# Schema.net
KiCad netlist of a schematic drawn in Altium Designer
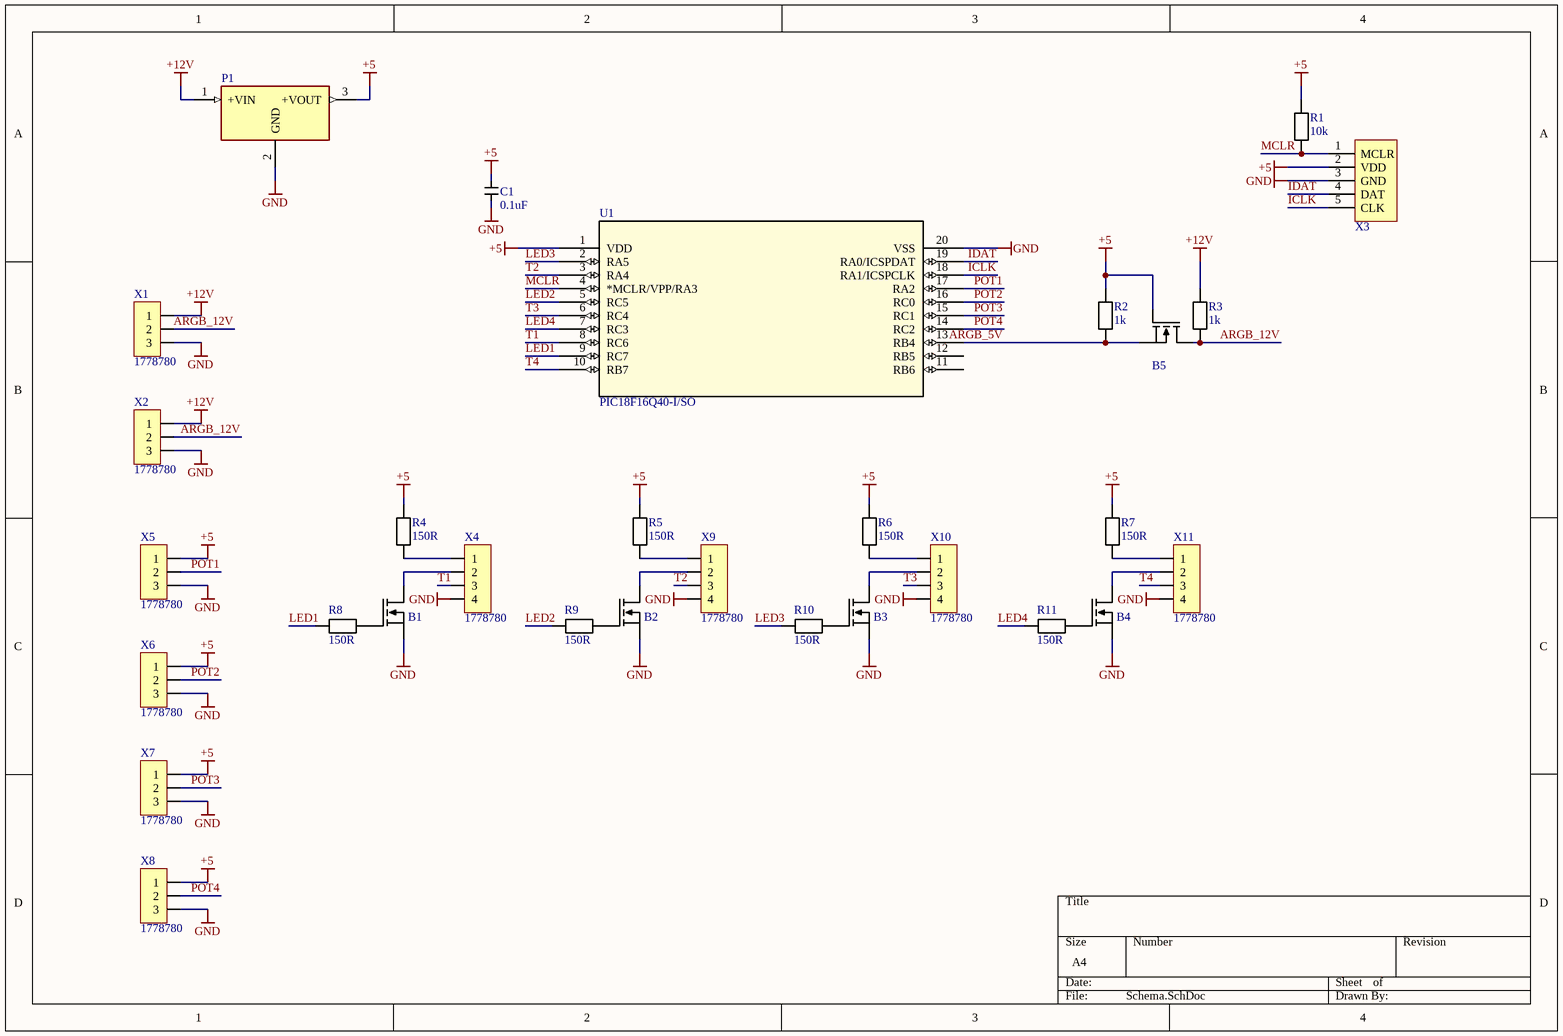
[diagram p0: Schema.SchDoc]

(export (version "E")
  (design (tool "Eeschema 10.0.6"))
  (components
    (comp (ref "B1")
      (value "N Kanal FET")
      (footprint "GeneralPCBLibrary:SOT23-3")
      (libsource (lib "GeneralSchemaLibrary") (part "N Kanal FET"))
    )
    (comp (ref "B2")
      (value "N Kanal FET")
      (footprint "GeneralPCBLibrary:SOT23-3")
      (libsource (lib "GeneralSchemaLibrary") (part "N Kanal FET"))
    )
    (comp (ref "B3")
      (value "N Kanal FET")
      (footprint "GeneralPCBLibrary:SOT23-3")
      (libsource (lib "GeneralSchemaLibrary") (part "N Kanal FET"))
    )
    (comp (ref "B4")
      (value "N Kanal FET")
      (footprint "GeneralPCBLibrary:SOT23-3")
      (libsource (lib "GeneralSchemaLibrary") (part "N Kanal FET"))
    )
    (comp (ref "B5")
      (value "N Kanal FET")
      (footprint "GeneralPCBLibrary:SOT23-3")
      (libsource (lib "GeneralSchemaLibrary") (part "N Kanal FET"))
    )
    (comp (ref "C1")
      (value "0.1uF")
      (footprint "GeneralPCBLibrary:CAP CER 0805 H")
      (fields (field (name "Comment") "Capacitor 0805"))
      (libsource (lib "GeneralSchemaLibrary") (part "Capacitor 0805"))
    )
    (comp (ref "P1")
      (value "TSR_1-2450")
      (footprint "GeneralPCBLibrary:TSR_1-2450")
      (description "1 Amp POL switching regulator, 4.6 to -36 VDC input, pos.-pos. circuit, LM78 compatible, SIP-3")
      (fields (field (name "MF") "Traco Power") (field (name "MP") "TSR 1-2450"))
      (libsource (lib "GeneralSchemaLibrary") (part "TSR_1-2450"))
    )
    (comp (ref "R1")
      (value "10k")
      (footprint "GeneralPCBLibrary:RES 0603 H")
      (fields (field (name "Comment") "Resistor 0603"))
      (libsource (lib "GeneralSchemaLibrary") (part "Resistor 0603"))
    )
    (comp (ref "R2")
      (value "1k")
      (footprint "GeneralPCBLibrary:RES 0603 H")
      (fields (field (name "Comment") "Resistor 0603"))
      (libsource (lib "GeneralSchemaLibrary") (part "Resistor 0603"))
    )
    (comp (ref "R3")
      (value "1k")
      (footprint "GeneralPCBLibrary:RES 0603 H")
      (fields (field (name "Comment") "Resistor 0603"))
      (libsource (lib "GeneralSchemaLibrary") (part "Resistor 0603"))
    )
    (comp (ref "R4")
      (value "150R")
      (footprint "GeneralPCBLibrary:RES 0603 H")
      (fields (field (name "Comment") "Resistor 0603"))
      (libsource (lib "GeneralSchemaLibrary") (part "Resistor 0603"))
    )
    (comp (ref "R5")
      (value "150R")
      (footprint "GeneralPCBLibrary:RES 0603 H")
      (fields (field (name "Comment") "Resistor 0603"))
      (libsource (lib "GeneralSchemaLibrary") (part "Resistor 0603"))
    )
    (comp (ref "R6")
      (value "150R")
      (footprint "GeneralPCBLibrary:RES 0603 H")
      (fields (field (name "Comment") "Resistor 0603"))
      (libsource (lib "GeneralSchemaLibrary") (part "Resistor 0603"))
    )
    (comp (ref "R7")
      (value "150R")
      (footprint "GeneralPCBLibrary:RES 0603 H")
      (fields (field (name "Comment") "Resistor 0603"))
      (libsource (lib "GeneralSchemaLibrary") (part "Resistor 0603"))
    )
    (comp (ref "R8")
      (value "150R")
      (footprint "GeneralPCBLibrary:RES 0603 H")
      (fields (field (name "Comment") "Resistor 0603"))
      (libsource (lib "GeneralSchemaLibrary") (part "Resistor 0603"))
    )
    (comp (ref "R9")
      (value "150R")
      (footprint "GeneralPCBLibrary:RES 0603 H")
      (fields (field (name "Comment") "Resistor 0603"))
      (libsource (lib "GeneralSchemaLibrary") (part "Resistor 0603"))
    )
    (comp (ref "R10")
      (value "150R")
      (footprint "GeneralPCBLibrary:RES 0603 H")
      (fields (field (name "Comment") "Resistor 0603"))
      (libsource (lib "GeneralSchemaLibrary") (part "Resistor 0603"))
    )
    (comp (ref "R11")
      (value "150R")
      (footprint "GeneralPCBLibrary:RES 0603 H")
      (fields (field (name "Comment") "Resistor 0603"))
      (libsource (lib "GeneralSchemaLibrary") (part "Resistor 0603"))
    )
    (comp (ref "U1")
      (value "PIC18F16Q40-I/SO")
      (footprint "GeneralPCBLibrary:SOIC20_SO_MCH-M")
      (description "No Description Available")
      (fields (field (name "COPYRIGHT") "Copyright (C) 2021 Ultra Librarian. All rights reserved."))
      (libsource (lib "GeneralSchemaLibrary") (part "PIC18F16Q40-I/SO"))
    )
    (comp (ref "X1")
      (value "1778780")
      (footprint "GeneralPCBLibrary:Phoenix 3Pos Header")
      (libsource (lib "GeneralSchemaLibrary") (part "Phoenix 3Pos Header"))
    )
    (comp (ref "X2")
      (value "1778780")
      (footprint "GeneralPCBLibrary:Phoenix 3Pos Header")
      (libsource (lib "GeneralSchemaLibrary") (part "Phoenix 3Pos Header"))
    )
    (comp (ref "X3")
      (value "ICSP")
      (footprint "5Pin_Header")
      (libsource (lib "GeneralSchemaLibrary") (part "ICSP"))
    )
    (comp (ref "X4")
      (value "1778780")
      (footprint "GeneralPCBLibrary:Phoenix 4Pos Header")
      (libsource (lib "GeneralSchemaLibrary") (part "Phoenix 4Pos Header"))
    )
    (comp (ref "X5")
      (value "1778780")
      (footprint "GeneralPCBLibrary:Phoenix 3Pos Header")
      (libsource (lib "GeneralSchemaLibrary") (part "Phoenix 3Pos Header"))
    )
    (comp (ref "X6")
      (value "1778780")
      (footprint "GeneralPCBLibrary:Phoenix 3Pos Header")
      (libsource (lib "GeneralSchemaLibrary") (part "Phoenix 3Pos Header"))
    )
    (comp (ref "X7")
      (value "1778780")
      (footprint "GeneralPCBLibrary:Phoenix 3Pos Header")
      (libsource (lib "GeneralSchemaLibrary") (part "Phoenix 3Pos Header"))
    )
    (comp (ref "X8")
      (value "1778780")
      (footprint "GeneralPCBLibrary:Phoenix 3Pos Header")
      (libsource (lib "GeneralSchemaLibrary") (part "Phoenix 3Pos Header"))
    )
    (comp (ref "X9")
      (value "1778780")
      (footprint "GeneralPCBLibrary:Phoenix 4Pos Header")
      (libsource (lib "GeneralSchemaLibrary") (part "Phoenix 4Pos Header"))
    )
    (comp (ref "X10")
      (value "1778780")
      (footprint "GeneralPCBLibrary:Phoenix 4Pos Header")
      (libsource (lib "GeneralSchemaLibrary") (part "Phoenix 4Pos Header"))
    )
    (comp (ref "X11")
      (value "1778780")
      (footprint "GeneralPCBLibrary:Phoenix 4Pos Header")
      (libsource (lib "GeneralSchemaLibrary") (part "Phoenix 4Pos Header"))
    )
  )
  (nets
    (net (code "1") (name "+5") (class "Default")
      (node (ref "B5") (pin "1") (pinfunction "Gate_1") (pintype "passive"))
      (node (ref "C1") (pin "2") (pinfunction "2_2") (pintype "passive"))
      (node (ref "P1") (pin "3") (pinfunction "+VOUT_3") (pintype "output"))
      (node (ref "R1") (pin "2") (pinfunction "2_2") (pintype "passive"))
      (node (ref "R2") (pin "2") (pinfunction "2_2") (pintype "passive"))
      (node (ref "R4") (pin "2") (pinfunction "2_2") (pintype "passive"))
      (node (ref "R5") (pin "2") (pinfunction "2_2") (pintype "passive"))
      (node (ref "R6") (pin "2") (pinfunction "2_2") (pintype "passive"))
      (node (ref "R7") (pin "2") (pinfunction "2_2") (pintype "passive"))
      (node (ref "U1") (pin "1") (pinfunction "VDD_1") (pintype "power_in"))
      (node (ref "X3") (pin "2") (pinfunction "VDD_2") (pintype "passive"))
      (node (ref "X5") (pin "1") (pinfunction "1_1") (pintype "passive"))
      (node (ref "X6") (pin "1") (pinfunction "1_1") (pintype "passive"))
      (node (ref "X7") (pin "1") (pinfunction "1_1") (pintype "passive"))
      (node (ref "X8") (pin "1") (pinfunction "1_1") (pintype "passive"))
    )
    (net (code "2") (name "+12V") (class "Default")
      (node (ref "P1") (pin "1") (pinfunction "+VIN_1") (pintype "input"))
      (node (ref "R3") (pin "2") (pinfunction "2_2") (pintype "passive"))
      (node (ref "X1") (pin "1") (pinfunction "1_1") (pintype "passive"))
      (node (ref "X2") (pin "1") (pinfunction "1_1") (pintype "passive"))
    )
    (net (code "3") (name "/ARGB_5V") (class "Default")
      (node (ref "B5") (pin "2") (pinfunction "Source_2") (pintype "passive"))
      (node (ref "R2") (pin "1") (pinfunction "1_1") (pintype "passive"))
      (node (ref "U1") (pin "13") (pinfunction "RB4_13") (pintype "bidirectional"))
    )
    (net (code "4") (name "/ARGB_12V") (class "Default")
      (node (ref "B5") (pin "3") (pinfunction "Drain_3") (pintype "passive"))
      (node (ref "R3") (pin "1") (pinfunction "1_1") (pintype "passive"))
      (node (ref "X1") (pin "2") (pinfunction "2_2") (pintype "passive"))
      (node (ref "X2") (pin "2") (pinfunction "2_2") (pintype "passive"))
    )
    (net (code "5") (name "/ICLK") (class "Default")
      (node (ref "U1") (pin "18") (pinfunction "RA1/ICSPCLK_18") (pintype "bidirectional"))
      (node (ref "X3") (pin "5") (pinfunction "CLK_5") (pintype "passive"))
    )
    (net (code "6") (name "/IDAT") (class "Default")
      (node (ref "U1") (pin "19") (pinfunction "RA0/ICSPDAT_19") (pintype "bidirectional"))
      (node (ref "X3") (pin "4") (pinfunction "DAT_4") (pintype "passive"))
    )
    (net (code "7") (name "/LED1") (class "Default")
      (node (ref "R8") (pin "2") (pinfunction "2_2") (pintype "passive"))
      (node (ref "U1") (pin "9") (pinfunction "RC7_9") (pintype "bidirectional"))
    )
    (net (code "8") (name "/LED2") (class "Default")
      (node (ref "R9") (pin "2") (pinfunction "2_2") (pintype "passive"))
      (node (ref "U1") (pin "5") (pinfunction "RC5_5") (pintype "bidirectional"))
    )
    (net (code "9") (name "/LED3") (class "Default")
      (node (ref "R10") (pin "2") (pinfunction "2_2") (pintype "passive"))
      (node (ref "U1") (pin "2") (pinfunction "RA5_2") (pintype "bidirectional"))
    )
    (net (code "10") (name "/LED4") (class "Default")
      (node (ref "R11") (pin "2") (pinfunction "2_2") (pintype "passive"))
      (node (ref "U1") (pin "7") (pinfunction "RC3_7") (pintype "bidirectional"))
    )
    (net (code "11") (name "/MCLR") (class "Default")
      (node (ref "R1") (pin "1") (pinfunction "1_1") (pintype "passive"))
      (node (ref "U1") (pin "4") (pinfunction "*MCLR/VPP/RA3_4") (pintype "bidirectional"))
      (node (ref "X3") (pin "1") (pinfunction "MCLR_1") (pintype "passive"))
    )
    (net (code "12") (name "/POT1") (class "Default")
      (node (ref "U1") (pin "17") (pinfunction "RA2_17") (pintype "bidirectional"))
      (node (ref "X5") (pin "2") (pinfunction "2_2") (pintype "passive"))
    )
    (net (code "13") (name "/POT2") (class "Default")
      (node (ref "U1") (pin "16") (pinfunction "RC0_16") (pintype "bidirectional"))
      (node (ref "X6") (pin "2") (pinfunction "2_2") (pintype "passive"))
    )
    (net (code "14") (name "/POT3") (class "Default")
      (node (ref "U1") (pin "15") (pinfunction "RC1_15") (pintype "bidirectional"))
      (node (ref "X7") (pin "2") (pinfunction "2_2") (pintype "passive"))
    )
    (net (code "15") (name "/POT4") (class "Default")
      (node (ref "U1") (pin "14") (pinfunction "RC2_14") (pintype "bidirectional"))
      (node (ref "X8") (pin "2") (pinfunction "2_2") (pintype "passive"))
    )
    (net (code "16") (name "/T1") (class "Default")
      (node (ref "U1") (pin "8") (pinfunction "RC6_8") (pintype "bidirectional"))
      (node (ref "X4") (pin "3") (pinfunction "3_3") (pintype "passive"))
    )
    (net (code "17") (name "/T2") (class "Default")
      (node (ref "U1") (pin "3") (pinfunction "RA4_3") (pintype "bidirectional"))
      (node (ref "X9") (pin "3") (pinfunction "3_3") (pintype "passive"))
    )
    (net (code "18") (name "/T3") (class "Default")
      (node (ref "U1") (pin "6") (pinfunction "RC4_6") (pintype "bidirectional"))
      (node (ref "X10") (pin "3") (pinfunction "3_3") (pintype "passive"))
    )
    (net (code "19") (name "/T4") (class "Default")
      (node (ref "U1") (pin "10") (pinfunction "RB7_10") (pintype "bidirectional"))
      (node (ref "X11") (pin "3") (pinfunction "3_3") (pintype "passive"))
    )
    (net (code "20") (name "GND") (class "Default")
      (node (ref "B1") (pin "2") (pinfunction "Source_2") (pintype "passive"))
      (node (ref "B2") (pin "2") (pinfunction "Source_2") (pintype "passive"))
      (node (ref "B3") (pin "2") (pinfunction "Source_2") (pintype "passive"))
      (node (ref "B4") (pin "2") (pinfunction "Source_2") (pintype "passive"))
      (node (ref "C1") (pin "1") (pinfunction "1_1") (pintype "passive"))
      (node (ref "P1") (pin "2") (pinfunction "GND_2") (pintype "power_in"))
      (node (ref "U1") (pin "20") (pinfunction "VSS_20") (pintype "passive"))
      (node (ref "X1") (pin "3") (pinfunction "3_3") (pintype "passive"))
      (node (ref "X10") (pin "4") (pinfunction "4_4") (pintype "passive"))
      (node (ref "X11") (pin "4") (pinfunction "4_4") (pintype "passive"))
      (node (ref "X2") (pin "3") (pinfunction "3_3") (pintype "passive"))
      (node (ref "X3") (pin "3") (pinfunction "GND_3") (pintype "passive"))
      (node (ref "X4") (pin "4") (pinfunction "4_4") (pintype "passive"))
      (node (ref "X5") (pin "3") (pinfunction "3_3") (pintype "passive"))
      (node (ref "X6") (pin "3") (pinfunction "3_3") (pintype "passive"))
      (node (ref "X7") (pin "3") (pinfunction "3_3") (pintype "passive"))
      (node (ref "X8") (pin "3") (pinfunction "3_3") (pintype "passive"))
      (node (ref "X9") (pin "4") (pinfunction "4_4") (pintype "passive"))
    )
    (net (code "21") (name "Net-(B1-Drain)") (class "Default")
      (node (ref "B1") (pin "3") (pinfunction "Drain_3") (pintype "passive"))
      (node (ref "X4") (pin "2") (pinfunction "2_2") (pintype "passive"))
    )
    (net (code "22") (name "Net-(B1-Gate)") (class "Default")
      (node (ref "B1") (pin "1") (pinfunction "Gate_1") (pintype "passive"))
      (node (ref "R8") (pin "1") (pinfunction "1_1") (pintype "passive"))
    )
    (net (code "23") (name "Net-(B2-Drain)") (class "Default")
      (node (ref "B2") (pin "3") (pinfunction "Drain_3") (pintype "passive"))
      (node (ref "X9") (pin "2") (pinfunction "2_2") (pintype "passive"))
    )
    (net (code "24") (name "Net-(B2-Gate)") (class "Default")
      (node (ref "B2") (pin "1") (pinfunction "Gate_1") (pintype "passive"))
      (node (ref "R9") (pin "1") (pinfunction "1_1") (pintype "passive"))
    )
    (net (code "25") (name "Net-(B3-Drain)") (class "Default")
      (node (ref "B3") (pin "3") (pinfunction "Drain_3") (pintype "passive"))
      (node (ref "X10") (pin "2") (pinfunction "2_2") (pintype "passive"))
    )
    (net (code "26") (name "Net-(B3-Gate)") (class "Default")
      (node (ref "B3") (pin "1") (pinfunction "Gate_1") (pintype "passive"))
      (node (ref "R10") (pin "1") (pinfunction "1_1") (pintype "passive"))
    )
    (net (code "27") (name "Net-(B4-Drain)") (class "Default")
      (node (ref "B4") (pin "3") (pinfunction "Drain_3") (pintype "passive"))
      (node (ref "X11") (pin "2") (pinfunction "2_2") (pintype "passive"))
    )
    (net (code "28") (name "Net-(B4-Gate)") (class "Default")
      (node (ref "B4") (pin "1") (pinfunction "Gate_1") (pintype "passive"))
      (node (ref "R11") (pin "1") (pinfunction "1_1") (pintype "passive"))
    )
    (net (code "29") (name "Net-(R4-Pad1)") (class "Default")
      (node (ref "R4") (pin "1") (pinfunction "1_1") (pintype "passive"))
      (node (ref "X4") (pin "1") (pinfunction "1_1") (pintype "passive"))
    )
    (net (code "30") (name "Net-(R5-Pad1)") (class "Default")
      (node (ref "R5") (pin "1") (pinfunction "1_1") (pintype "passive"))
      (node (ref "X9") (pin "1") (pinfunction "1_1") (pintype "passive"))
    )
    (net (code "31") (name "Net-(R6-Pad1)") (class "Default")
      (node (ref "R6") (pin "1") (pinfunction "1_1") (pintype "passive"))
      (node (ref "X10") (pin "1") (pinfunction "1_1") (pintype "passive"))
    )
    (net (code "32") (name "Net-(R7-Pad1)") (class "Default")
      (node (ref "R7") (pin "1") (pinfunction "1_1") (pintype "passive"))
      (node (ref "X11") (pin "1") (pinfunction "1_1") (pintype "passive"))
    )
    (net (code "33") (name "unconnected-(U1-RB5-Pad12)") (class "Default")
      (node (ref "U1") (pin "12") (pinfunction "RB5_12") (pintype "bidirectional"))
    )
    (net (code "34") (name "unconnected-(U1-RB6-Pad11)") (class "Default")
      (node (ref "U1") (pin "11") (pinfunction "RB6_11") (pintype "bidirectional"))
    )
  )
)
